# bucket-banging.net
KiCad netlist of a schematic drawn in EAGLE
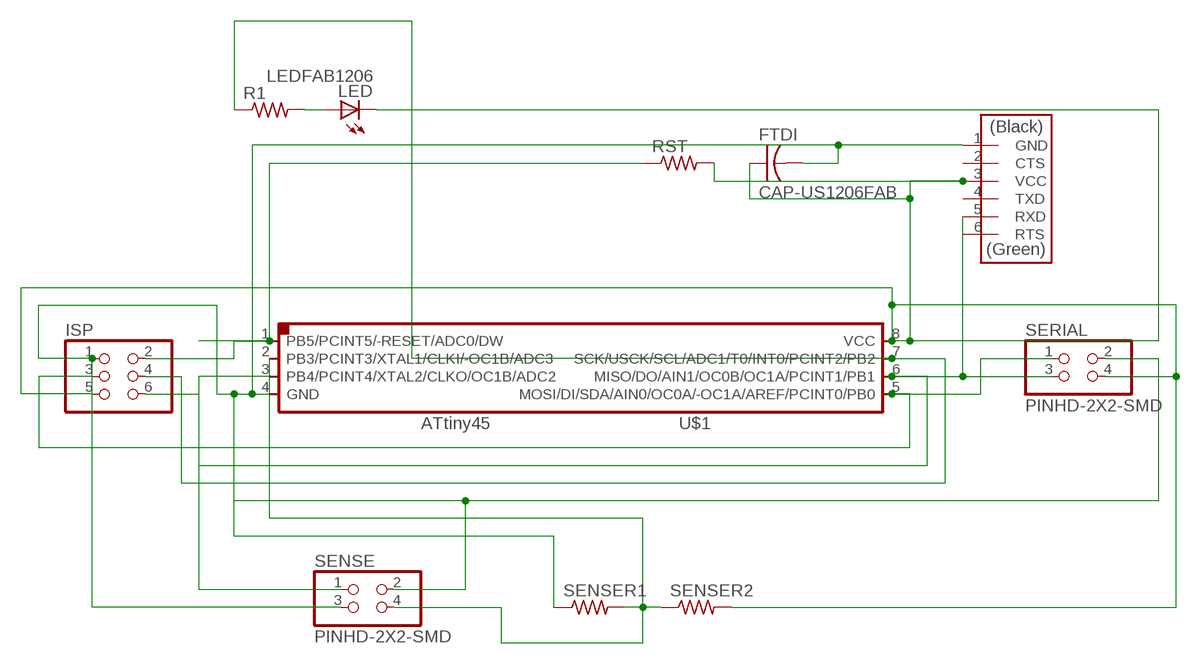
[diagram p0: schematic, sheet 1]

(export (version "E")
  (design (tool "Eeschema 10.0.6"))
  (components
    (comp (ref "FTDI")
      (value "CAP-US1206FAB")
      (footprint "eagle-import:C1206FAB")
      (libsource (lib "eagle-import") (part "CAP-US1206FAB"))
    )
    (comp (ref "ISP")
      (value "PINHD-2X3-SMD")
      (footprint "eagle-import:2X03SMD")
      (libsource (lib "eagle-import") (part "PINHD-2X3-SMD"))
    )
    (comp (ref "LED")
      (value "LEDFAB1206")
      (footprint "eagle-import:LED1206FAB")
      (libsource (lib "eagle-import") (part "LEDFAB1206"))
    )
    (comp (ref "R1")
      (value "RES-US1206FAB")
      (footprint "eagle-import:R1206FAB")
      (libsource (lib "eagle-import") (part "RES-US1206FAB"))
    )
    (comp (ref "RST")
      (value "RES-US1206FAB")
      (footprint "eagle-import:R1206FAB")
      (libsource (lib "eagle-import") (part "RES-US1206FAB"))
    )
    (comp (ref "SENSE")
      (value "PINHD-2X2-SMD")
      (footprint "eagle-import:2X02SMD")
      (libsource (lib "eagle-import") (part "PINHD-2X2-SMD"))
    )
    (comp (ref "SENSER1")
      (value "RES-US1206FAB")
      (footprint "eagle-import:R1206FAB")
      (libsource (lib "eagle-import") (part "RES-US1206FAB"))
    )
    (comp (ref "SENSER2")
      (value "RES-US1206FAB")
      (footprint "eagle-import:R1206FAB")
      (libsource (lib "eagle-import") (part "RES-US1206FAB"))
    )
    (comp (ref "SERIAL")
      (value "PINHD-2X2-SMD")
      (footprint "eagle-import:2X02SMD")
      (libsource (lib "eagle-import") (part "PINHD-2X2-SMD"))
    )
    (comp (ref "U$1")
      (value "ATTINY45SI")
      (footprint "eagle-import:SOIC8")
      (libsource (lib "eagle-import") (part "ATTINY45SI"))
    )
    (comp (ref "U$2")
      (value "FTDI-SMD-HEADER")
      (footprint "eagle-import:1X06SMD")
      (libsource (lib "eagle-import") (part "FTDI-SMD-HEADER"))
    )
  )
  (nets
    (net (code "1") (name "Net-(LED-A)") (class "Default")
      (node (ref "LED") (pin "1") (pinfunction "A_1") (pintype "passive"))
      (node (ref "R1") (pin "2") (pinfunction "2_2") (pintype "passive"))
    )
    (net (code "2") (name "Net-(LED-C)") (class "Default")
      (node (ref "FTDI") (pin "1") (pinfunction "1_1") (pintype "passive"))
      (node (ref "ISP") (pin "5") (pinfunction "5_5") (pintype "passive"))
      (node (ref "LED") (pin "2") (pinfunction "C_2") (pintype "passive"))
      (node (ref "RST") (pin "2") (pinfunction "2_2") (pintype "passive"))
      (node (ref "SENSER2") (pin "2") (pinfunction "2_2") (pintype "passive"))
      (node (ref "SERIAL") (pin "4") (pinfunction "4_4") (pintype "passive"))
      (node (ref "U$1") (pin "8") (pinfunction "VCC_8") (pintype "bidirectional"))
      (node (ref "U$2") (pin "3") (pinfunction "VCC_3") (pintype "bidirectional"))
    )
    (net (code "3") (name "Net-(U$1-GND)") (class "Default")
      (node (ref "FTDI") (pin "2") (pinfunction "2_2") (pintype "passive"))
      (node (ref "ISP") (pin "1") (pinfunction "1_1") (pintype "passive"))
      (node (ref "SENSE") (pin "2") (pinfunction "2_2") (pintype "passive"))
      (node (ref "SENSE") (pin "3") (pinfunction "3_3") (pintype "passive"))
      (node (ref "SENSER1") (pin "1") (pinfunction "1_1") (pintype "passive"))
      (node (ref "SERIAL") (pin "2") (pinfunction "2_2") (pintype "passive"))
      (node (ref "U$1") (pin "4") (pinfunction "GND_4") (pintype "bidirectional"))
      (node (ref "U$2") (pin "1") (pinfunction "GND_1") (pintype "bidirectional"))
    )
    (net (code "4") (name "Net-(U$1-MISO{slash}DO{slash}AIN1{slash}OC0B{slash}OC1A{slash}PCINT1{slash}PB1)") (class "Default")
      (node (ref "ISP") (pin "6") (pinfunction "6_6") (pintype "passive"))
      (node (ref "SERIAL") (pin "3") (pinfunction "3_3") (pintype "passive"))
      (node (ref "U$1") (pin "6") (pinfunction "MISO/DO/AIN1/OC0B/OC1A/PCINT1/PB1_6") (pintype "bidirectional"))
      (node (ref "U$2") (pin "5") (pinfunction "RXD_5") (pintype "bidirectional"))
    )
    (net (code "5") (name "Net-(U$1-MOSI{slash}DI{slash}SDA{slash}AIN0{slash}OC0A{slash}-OC1A{slash}AREF{slash}PCINT0{slash}PB0)") (class "Default")
      (node (ref "ISP") (pin "3") (pinfunction "3_3") (pintype "passive"))
      (node (ref "SERIAL") (pin "1") (pinfunction "1_1") (pintype "passive"))
      (node (ref "U$1") (pin "5") (pinfunction "MOSI/DI/SDA/AIN0/OC0A/-OC1A/AREF/PCINT0/PB0_5") (pintype "bidirectional"))
    )
    (net (code "6") (name "Net-(U$1-PB3{slash}PCINT3{slash}XTAL1{slash}CLKI{slash}-OC1B{slash}ADC3)") (class "Default")
      (node (ref "SENSE") (pin "4") (pinfunction "4_4") (pintype "passive"))
      (node (ref "SENSER1") (pin "2") (pinfunction "2_2") (pintype "passive"))
      (node (ref "SENSER2") (pin "1") (pinfunction "1_1") (pintype "passive"))
      (node (ref "U$1") (pin "2") (pinfunction "PB3/PCINT3/XTAL1/CLKI/-OC1B/ADC3_2") (pintype "bidirectional"))
    )
    (net (code "7") (name "Net-(U$1-PB4{slash}PCINT4{slash}XTAL2{slash}CLKO{slash}OC1B{slash}ADC2)") (class "Default")
      (node (ref "SENSE") (pin "1") (pinfunction "1_1") (pintype "passive"))
      (node (ref "U$1") (pin "3") (pinfunction "PB4/PCINT4/XTAL2/CLKO/OC1B/ADC2_3") (pintype "bidirectional"))
    )
    (net (code "8") (name "Net-(U$1-PB5{slash}PCINT5{slash}-RESET{slash}ADC0{slash}DW)") (class "Default")
      (node (ref "ISP") (pin "2") (pinfunction "2_2") (pintype "passive"))
      (node (ref "RST") (pin "1") (pinfunction "1_1") (pintype "passive"))
      (node (ref "U$1") (pin "1") (pinfunction "PB5/PCINT5/-RESET/ADC0/DW_1") (pintype "bidirectional"))
    )
    (net (code "9") (name "Net-(U$1-SCK{slash}USCK{slash}SCL{slash}ADC1{slash}T0{slash}INT0{slash}PCINT2{slash}PB2)") (class "Default")
      (node (ref "ISP") (pin "4") (pinfunction "4_4") (pintype "passive"))
      (node (ref "R1") (pin "1") (pinfunction "1_1") (pintype "passive"))
      (node (ref "U$1") (pin "7") (pinfunction "SCK/USCK/SCL/ADC1/T0/INT0/PCINT2/PB2_7") (pintype "bidirectional"))
    )
    (net (code "10") (name "unconnected-(U$2-CTS-Pad2)") (class "Default")
      (node (ref "U$2") (pin "2") (pinfunction "CTS_2") (pintype "bidirectional"))
    )
    (net (code "11") (name "unconnected-(U$2-RTS-Pad6)") (class "Default")
      (node (ref "U$2") (pin "6") (pinfunction "RTS_6") (pintype "bidirectional"))
    )
    (net (code "12") (name "unconnected-(U$2-TXD-Pad4)") (class "Default")
      (node (ref "U$2") (pin "4") (pinfunction "TXD_4") (pintype "bidirectional"))
    )
  )
)
